# 00_Main.net
KiCad netlist of a schematic drawn in Altium Designer
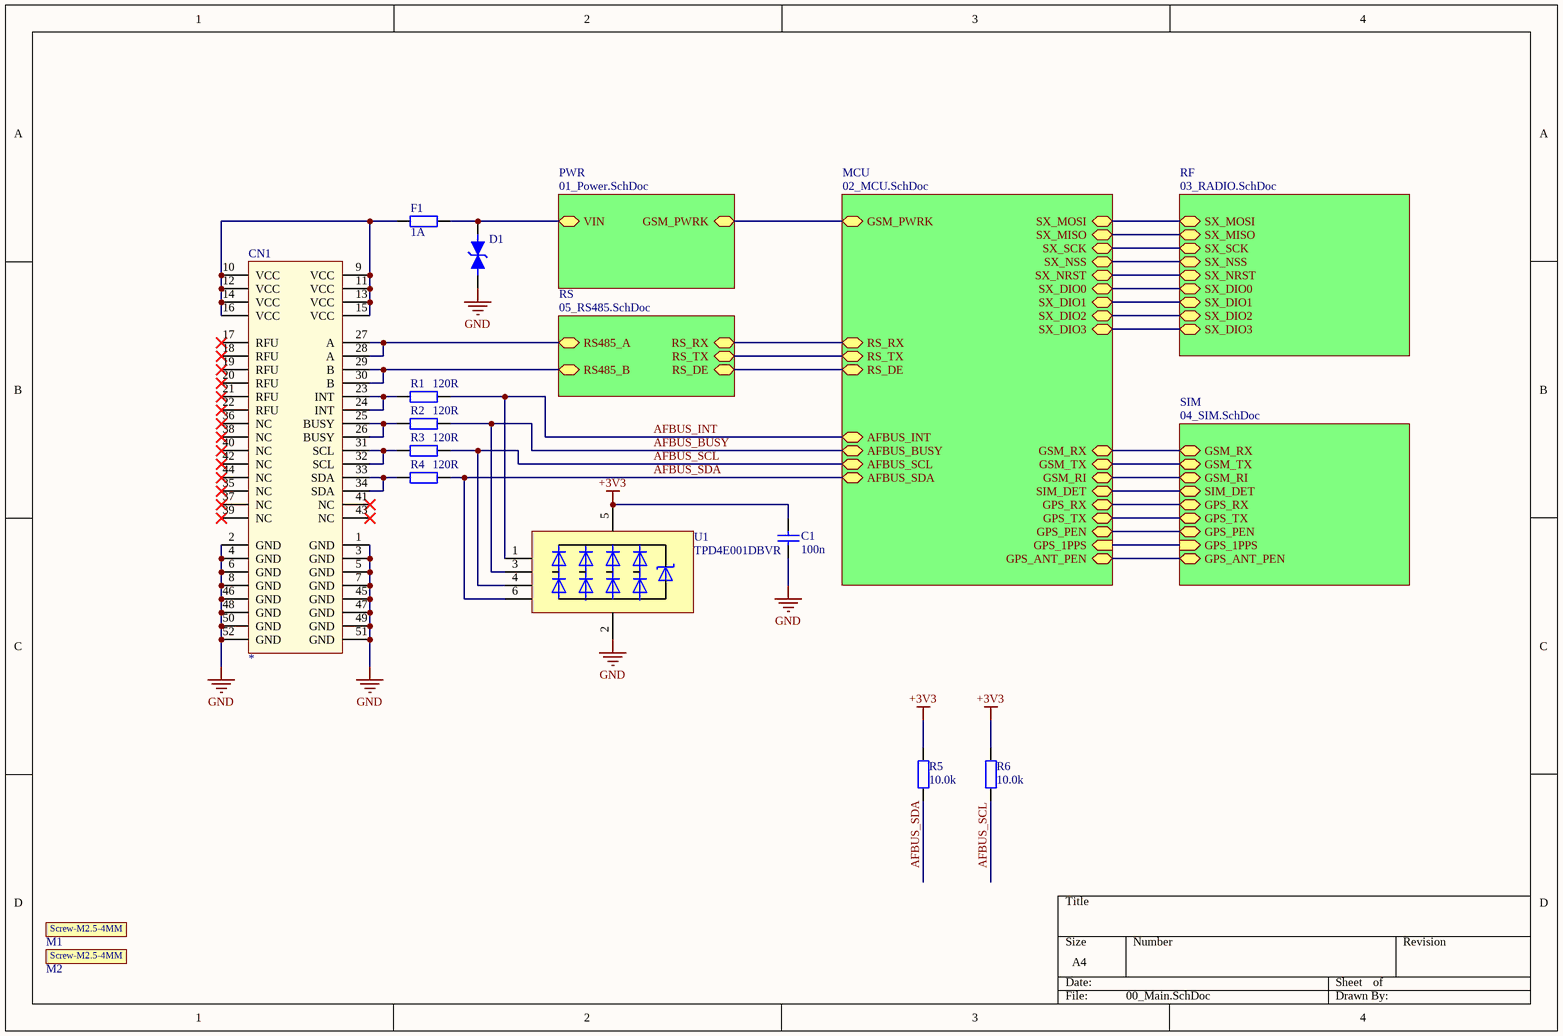
[diagram p0: 00_Main.SchDoc]

(export (version "E")
  (design (tool "Eeschema 10.0.6"))
  (components
    (comp (ref "C1")
      (value "100n")
      (footprint "C0603_IPC_MD")
      (description "CAP CER 0.1UF 16V X7R 0603")
      (fields
        (field (name "MANUFACTURER") "Samsung Electro-Mechanics")
        (field (name "MANUFACTURER PART NUMBER") "CL10B104KO8WPNC")
      )
      (libsource (lib "alfasat_lib") (part "CL10B104KO8WPNC"))
    )
    (comp (ref "CN1")
      (value "*")
      (footprint "PCI-E-MINI")
      (description "EDGE CONN PCI EXP MINI 52POS")
      (libsource (lib "alfasat_lib") (part "ALAFASAT_TRX_EDGE_CONN"))
    )
    (comp (ref "D1")
      (value "824501121")
      (footprint "DIOM4227X25N")
      (description "TVS DIODE 12V 19.9V DO214AC")
      (fields (field (name "MANUFACTURER") "Wurth Electronics Inc."))
      (libsource (lib "alfasat_lib_eps") (part "824501121_TVS"))
    )
    (comp (ref "F1")
      (value "1A")
      (footprint "R0603_IPC_MD")
      (description "FUSE BOARD MOUNT 1A 32VDC 0603")
      (fields
        (field (name "MANUFACTURER") "Bourns Inc.")
        (field (name "MANUFACTURER PART NUMBER") "MFU0603FF01000P500")
      )
      (libsource (lib "alfasat_lib") (part "MFU0603FF01000P500"))
    )
    (comp (ref "M1")
      (value "Screw-M2.5-4MM")
      (fields (field (name "MANUFACTURER") "China"))
      (libsource (lib "alfasat_lib") (part "Screw-M2.5-4MM"))
    )
    (comp (ref "M2")
      (value "Screw-M2.5-4MM")
      (fields (field (name "MANUFACTURER") "China"))
      (libsource (lib "alfasat_lib") (part "Screw-M2.5-4MM"))
    )
    (comp (ref "R1")
      (value "120R")
      (footprint "R0603_IPC_MD")
      (description "RES SMD 120 OHM 5% 1/10W 0603")
      (fields
        (field (name "MANUFACTURER") "Yageo")
        (field (name "MANUFACTURER PART NUMBER") "RC0603JR-07120RL")
      )
      (libsource (lib "alfasat_lib") (part "RC0603JR-07120RL"))
    )
    (comp (ref "R2")
      (value "120R")
      (footprint "R0603_IPC_MD")
      (description "RES SMD 120 OHM 5% 1/10W 0603")
      (fields
        (field (name "MANUFACTURER") "Yageo")
        (field (name "MANUFACTURER PART NUMBER") "RC0603JR-07120RL")
      )
      (libsource (lib "alfasat_lib") (part "RC0603JR-07120RL"))
    )
    (comp (ref "R3")
      (value "120R")
      (footprint "R0603_IPC_MD")
      (description "RES SMD 120 OHM 5% 1/10W 0603")
      (fields
        (field (name "MANUFACTURER") "Yageo")
        (field (name "MANUFACTURER PART NUMBER") "RC0603JR-07120RL")
      )
      (libsource (lib "alfasat_lib") (part "RC0603JR-07120RL"))
    )
    (comp (ref "R4")
      (value "120R")
      (footprint "R0603_IPC_MD")
      (description "RES SMD 120 OHM 5% 1/10W 0603")
      (fields
        (field (name "MANUFACTURER") "Yageo")
        (field (name "MANUFACTURER PART NUMBER") "RC0603JR-07120RL")
      )
      (libsource (lib "alfasat_lib") (part "RC0603JR-07120RL"))
    )
    (comp (ref "R5")
      (value "10.0k")
      (footprint "R0603_IPC_MD")
      (description "RES 10K OHM 1% 1/10W 0603")
      (fields
        (field (name "MANUFACTURER") "Stackpole Electronics Inc")
        (field (name "MANUFACTURER PART NUMBER") "RMCF0603FT10K0")
      )
      (libsource (lib "alfasat_lib_eps") (part "RMCF0603FT10K0"))
    )
    (comp (ref "R6")
      (value "10.0k")
      (footprint "R0603_IPC_MD")
      (description "RES 10K OHM 1% 1/10W 0603")
      (fields
        (field (name "MANUFACTURER") "Stackpole Electronics Inc")
        (field (name "MANUFACTURER PART NUMBER") "RMCF0603FT10K0")
      )
      (libsource (lib "alfasat_lib") (part "RMCF0603FT10K0"))
    )
    (comp (ref "U1")
      (value "TPD4E001DBVR")
      (footprint "SOT23-6")
      (description "4x TVS DIODE 5.5V SOT23-6")
      (fields (field (name "MANUFACTURER") "TI"))
      (libsource (lib "alfasat_lib") (part "TPD4E001DBVR"))
    )
  )
  (nets
    (net (code "1") (name "+3V3") (class "Default")
      (node (ref "C1") (pin "1") (pinfunction "1_1") (pintype "passive"))
      (node (ref "R5") (pin "2") (pinfunction "2_2") (pintype "passive"))
      (node (ref "R6") (pin "2") (pinfunction "2_2") (pintype "passive"))
      (node (ref "U1") (pin "5") (pinfunction "VCC_5") (pintype "power_in"))
    )
    (net (code "2") (name "/AFBUS_BUSY") (class "Default")
      (node (ref "R2") (pin "2") (pinfunction "2_2") (pintype "passive"))
      (node (ref "U1") (pin "3") (pinfunction "IO2_3") (pintype "passive"))
    )
    (net (code "3") (name "/AFBUS_INT") (class "Default")
      (node (ref "R1") (pin "2") (pinfunction "2_2") (pintype "passive"))
      (node (ref "U1") (pin "1") (pinfunction "IO1_1") (pintype "passive"))
    )
    (net (code "4") (name "/AFBUS_SCL") (class "Default")
      (node (ref "R3") (pin "2") (pinfunction "2_2") (pintype "passive"))
      (node (ref "R6") (pin "1") (pinfunction "1_1") (pintype "passive"))
      (node (ref "U1") (pin "4") (pinfunction "IO3_4") (pintype "passive"))
    )
    (net (code "5") (name "/AFBUS_SDA") (class "Default")
      (node (ref "R4") (pin "2") (pinfunction "2_2") (pintype "passive"))
      (node (ref "R5") (pin "1") (pinfunction "1_1") (pintype "passive"))
      (node (ref "U1") (pin "6") (pinfunction "IO4_6") (pintype "passive"))
    )
    (net (code "15") (name "/RS485_A") (class "Default")
      (node (ref "CN1") (pin "27") (pinfunction "A_27") (pintype "passive"))
      (node (ref "CN1") (pin "28") (pinfunction "A_28") (pintype "passive"))
    )
    (net (code "16") (name "/RS485_B") (class "Default")
      (node (ref "CN1") (pin "29") (pinfunction "B_29") (pintype "passive"))
      (node (ref "CN1") (pin "30") (pinfunction "B_30") (pintype "passive"))
    )
    (net (code "30") (name "/VIN") (class "Default")
      (node (ref "D1") (pin "2") (pinfunction "2_2") (pintype "passive"))
      (node (ref "F1") (pin "2") (pinfunction "2_2") (pintype "passive"))
    )
    (net (code "31") (name "GND") (class "Default")
      (node (ref "C1") (pin "2") (pinfunction "2_2") (pintype "passive"))
      (node (ref "CN1") (pin "1") (pinfunction "GND_1") (pintype "passive"))
      (node (ref "CN1") (pin "2") (pinfunction "GND_2") (pintype "passive"))
      (node (ref "CN1") (pin "3") (pinfunction "GND_3") (pintype "passive"))
      (node (ref "CN1") (pin "4") (pinfunction "GND_4") (pintype "passive"))
      (node (ref "CN1") (pin "45") (pinfunction "GND_45") (pintype "passive"))
      (node (ref "CN1") (pin "46") (pinfunction "GND_46") (pintype "passive"))
      (node (ref "CN1") (pin "47") (pinfunction "GND_47") (pintype "passive"))
      (node (ref "CN1") (pin "48") (pinfunction "GND_48") (pintype "passive"))
      (node (ref "CN1") (pin "49") (pinfunction "GND_49") (pintype "passive"))
      (node (ref "CN1") (pin "5") (pinfunction "GND_5") (pintype "passive"))
      (node (ref "CN1") (pin "50") (pinfunction "GND_50") (pintype "passive"))
      (node (ref "CN1") (pin "51") (pinfunction "GND_51") (pintype "passive"))
      (node (ref "CN1") (pin "52") (pinfunction "GND_52") (pintype "passive"))
      (node (ref "CN1") (pin "6") (pinfunction "GND_6") (pintype "passive"))
      (node (ref "CN1") (pin "7") (pinfunction "GND_7") (pintype "passive"))
      (node (ref "CN1") (pin "8") (pinfunction "GND_8") (pintype "passive"))
      (node (ref "D1") (pin "1") (pinfunction "1_1") (pintype "passive"))
      (node (ref "U1") (pin "2") (pinfunction "GND_2") (pintype "power_in"))
    )
    (net (code "32") (name "Net-(CN1-BUSY-Pad25)") (class "Default")
      (node (ref "CN1") (pin "25") (pinfunction "BUSY_25") (pintype "passive"))
      (node (ref "CN1") (pin "26") (pinfunction "BUSY_26") (pintype "passive"))
      (node (ref "R2") (pin "1") (pinfunction "1_1") (pintype "passive"))
    )
    (net (code "33") (name "Net-(CN1-INT-Pad23)") (class "Default")
      (node (ref "CN1") (pin "23") (pinfunction "INT_23") (pintype "passive"))
      (node (ref "CN1") (pin "24") (pinfunction "INT_24") (pintype "passive"))
      (node (ref "R1") (pin "1") (pinfunction "1_1") (pintype "passive"))
    )
    (net (code "34") (name "Net-(CN1-SCL-Pad31)") (class "Default")
      (node (ref "CN1") (pin "31") (pinfunction "SCL_31") (pintype "passive"))
      (node (ref "CN1") (pin "32") (pinfunction "SCL_32") (pintype "passive"))
      (node (ref "R3") (pin "1") (pinfunction "1_1") (pintype "passive"))
    )
    (net (code "35") (name "Net-(CN1-SDA-Pad33)") (class "Default")
      (node (ref "CN1") (pin "33") (pinfunction "SDA_33") (pintype "passive"))
      (node (ref "CN1") (pin "34") (pinfunction "SDA_34") (pintype "passive"))
      (node (ref "R4") (pin "1") (pinfunction "1_1") (pintype "passive"))
    )
    (net (code "36") (name "Net-(CN1-VCC-Pad10)") (class "Default")
      (node (ref "CN1") (pin "10") (pinfunction "VCC_10") (pintype "passive"))
      (node (ref "CN1") (pin "11") (pinfunction "VCC_11") (pintype "passive"))
      (node (ref "CN1") (pin "12") (pinfunction "VCC_12") (pintype "passive"))
      (node (ref "CN1") (pin "13") (pinfunction "VCC_13") (pintype "passive"))
      (node (ref "CN1") (pin "14") (pinfunction "VCC_14") (pintype "passive"))
      (node (ref "CN1") (pin "15") (pinfunction "VCC_15") (pintype "passive"))
      (node (ref "CN1") (pin "16") (pinfunction "VCC_16") (pintype "passive"))
      (node (ref "CN1") (pin "9") (pinfunction "VCC_9") (pintype "passive"))
      (node (ref "F1") (pin "1") (pinfunction "1_1") (pintype "passive"))
    )
    (net (code "37") (name "unconnected-(CN1-NC-Pad35)") (class "Default")
      (node (ref "CN1") (pin "35") (pinfunction "NC_35") (pintype "passive+no_connect"))
    )
    (net (code "38") (name "unconnected-(CN1-NC-Pad36)") (class "Default")
      (node (ref "CN1") (pin "36") (pinfunction "NC_36") (pintype "passive+no_connect"))
    )
    (net (code "39") (name "unconnected-(CN1-NC-Pad37)") (class "Default")
      (node (ref "CN1") (pin "37") (pinfunction "NC_37") (pintype "passive+no_connect"))
    )
    (net (code "40") (name "unconnected-(CN1-NC-Pad38)") (class "Default")
      (node (ref "CN1") (pin "38") (pinfunction "NC_38") (pintype "passive+no_connect"))
    )
    (net (code "41") (name "unconnected-(CN1-NC-Pad39)") (class "Default")
      (node (ref "CN1") (pin "39") (pinfunction "NC_39") (pintype "passive+no_connect"))
    )
    (net (code "42") (name "unconnected-(CN1-NC-Pad40)") (class "Default")
      (node (ref "CN1") (pin "40") (pinfunction "NC_40") (pintype "passive+no_connect"))
    )
    (net (code "43") (name "unconnected-(CN1-NC-Pad41)") (class "Default")
      (node (ref "CN1") (pin "41") (pinfunction "NC_41") (pintype "passive+no_connect"))
    )
    (net (code "44") (name "unconnected-(CN1-NC-Pad42)") (class "Default")
      (node (ref "CN1") (pin "42") (pinfunction "NC_42") (pintype "passive+no_connect"))
    )
    (net (code "45") (name "unconnected-(CN1-NC-Pad43)") (class "Default")
      (node (ref "CN1") (pin "43") (pinfunction "NC_43") (pintype "passive+no_connect"))
    )
    (net (code "46") (name "unconnected-(CN1-NC-Pad44)") (class "Default")
      (node (ref "CN1") (pin "44") (pinfunction "NC_44") (pintype "passive+no_connect"))
    )
    (net (code "47") (name "unconnected-(CN1-RFU-Pad17)") (class "Default")
      (node (ref "CN1") (pin "17") (pinfunction "RFU_17") (pintype "passive+no_connect"))
    )
    (net (code "48") (name "unconnected-(CN1-RFU-Pad18)") (class "Default")
      (node (ref "CN1") (pin "18") (pinfunction "RFU_18") (pintype "passive+no_connect"))
    )
    (net (code "49") (name "unconnected-(CN1-RFU-Pad19)") (class "Default")
      (node (ref "CN1") (pin "19") (pinfunction "RFU_19") (pintype "passive+no_connect"))
    )
    (net (code "50") (name "unconnected-(CN1-RFU-Pad20)") (class "Default")
      (node (ref "CN1") (pin "20") (pinfunction "RFU_20") (pintype "passive+no_connect"))
    )
    (net (code "51") (name "unconnected-(CN1-RFU-Pad21)") (class "Default")
      (node (ref "CN1") (pin "21") (pinfunction "RFU_21") (pintype "passive+no_connect"))
    )
    (net (code "52") (name "unconnected-(CN1-RFU-Pad22)") (class "Default")
      (node (ref "CN1") (pin "22") (pinfunction "RFU_22") (pintype "passive+no_connect"))
    )
  )
)
